# Schematics.net
KiCad netlist of a schematic drawn in EasyEDA
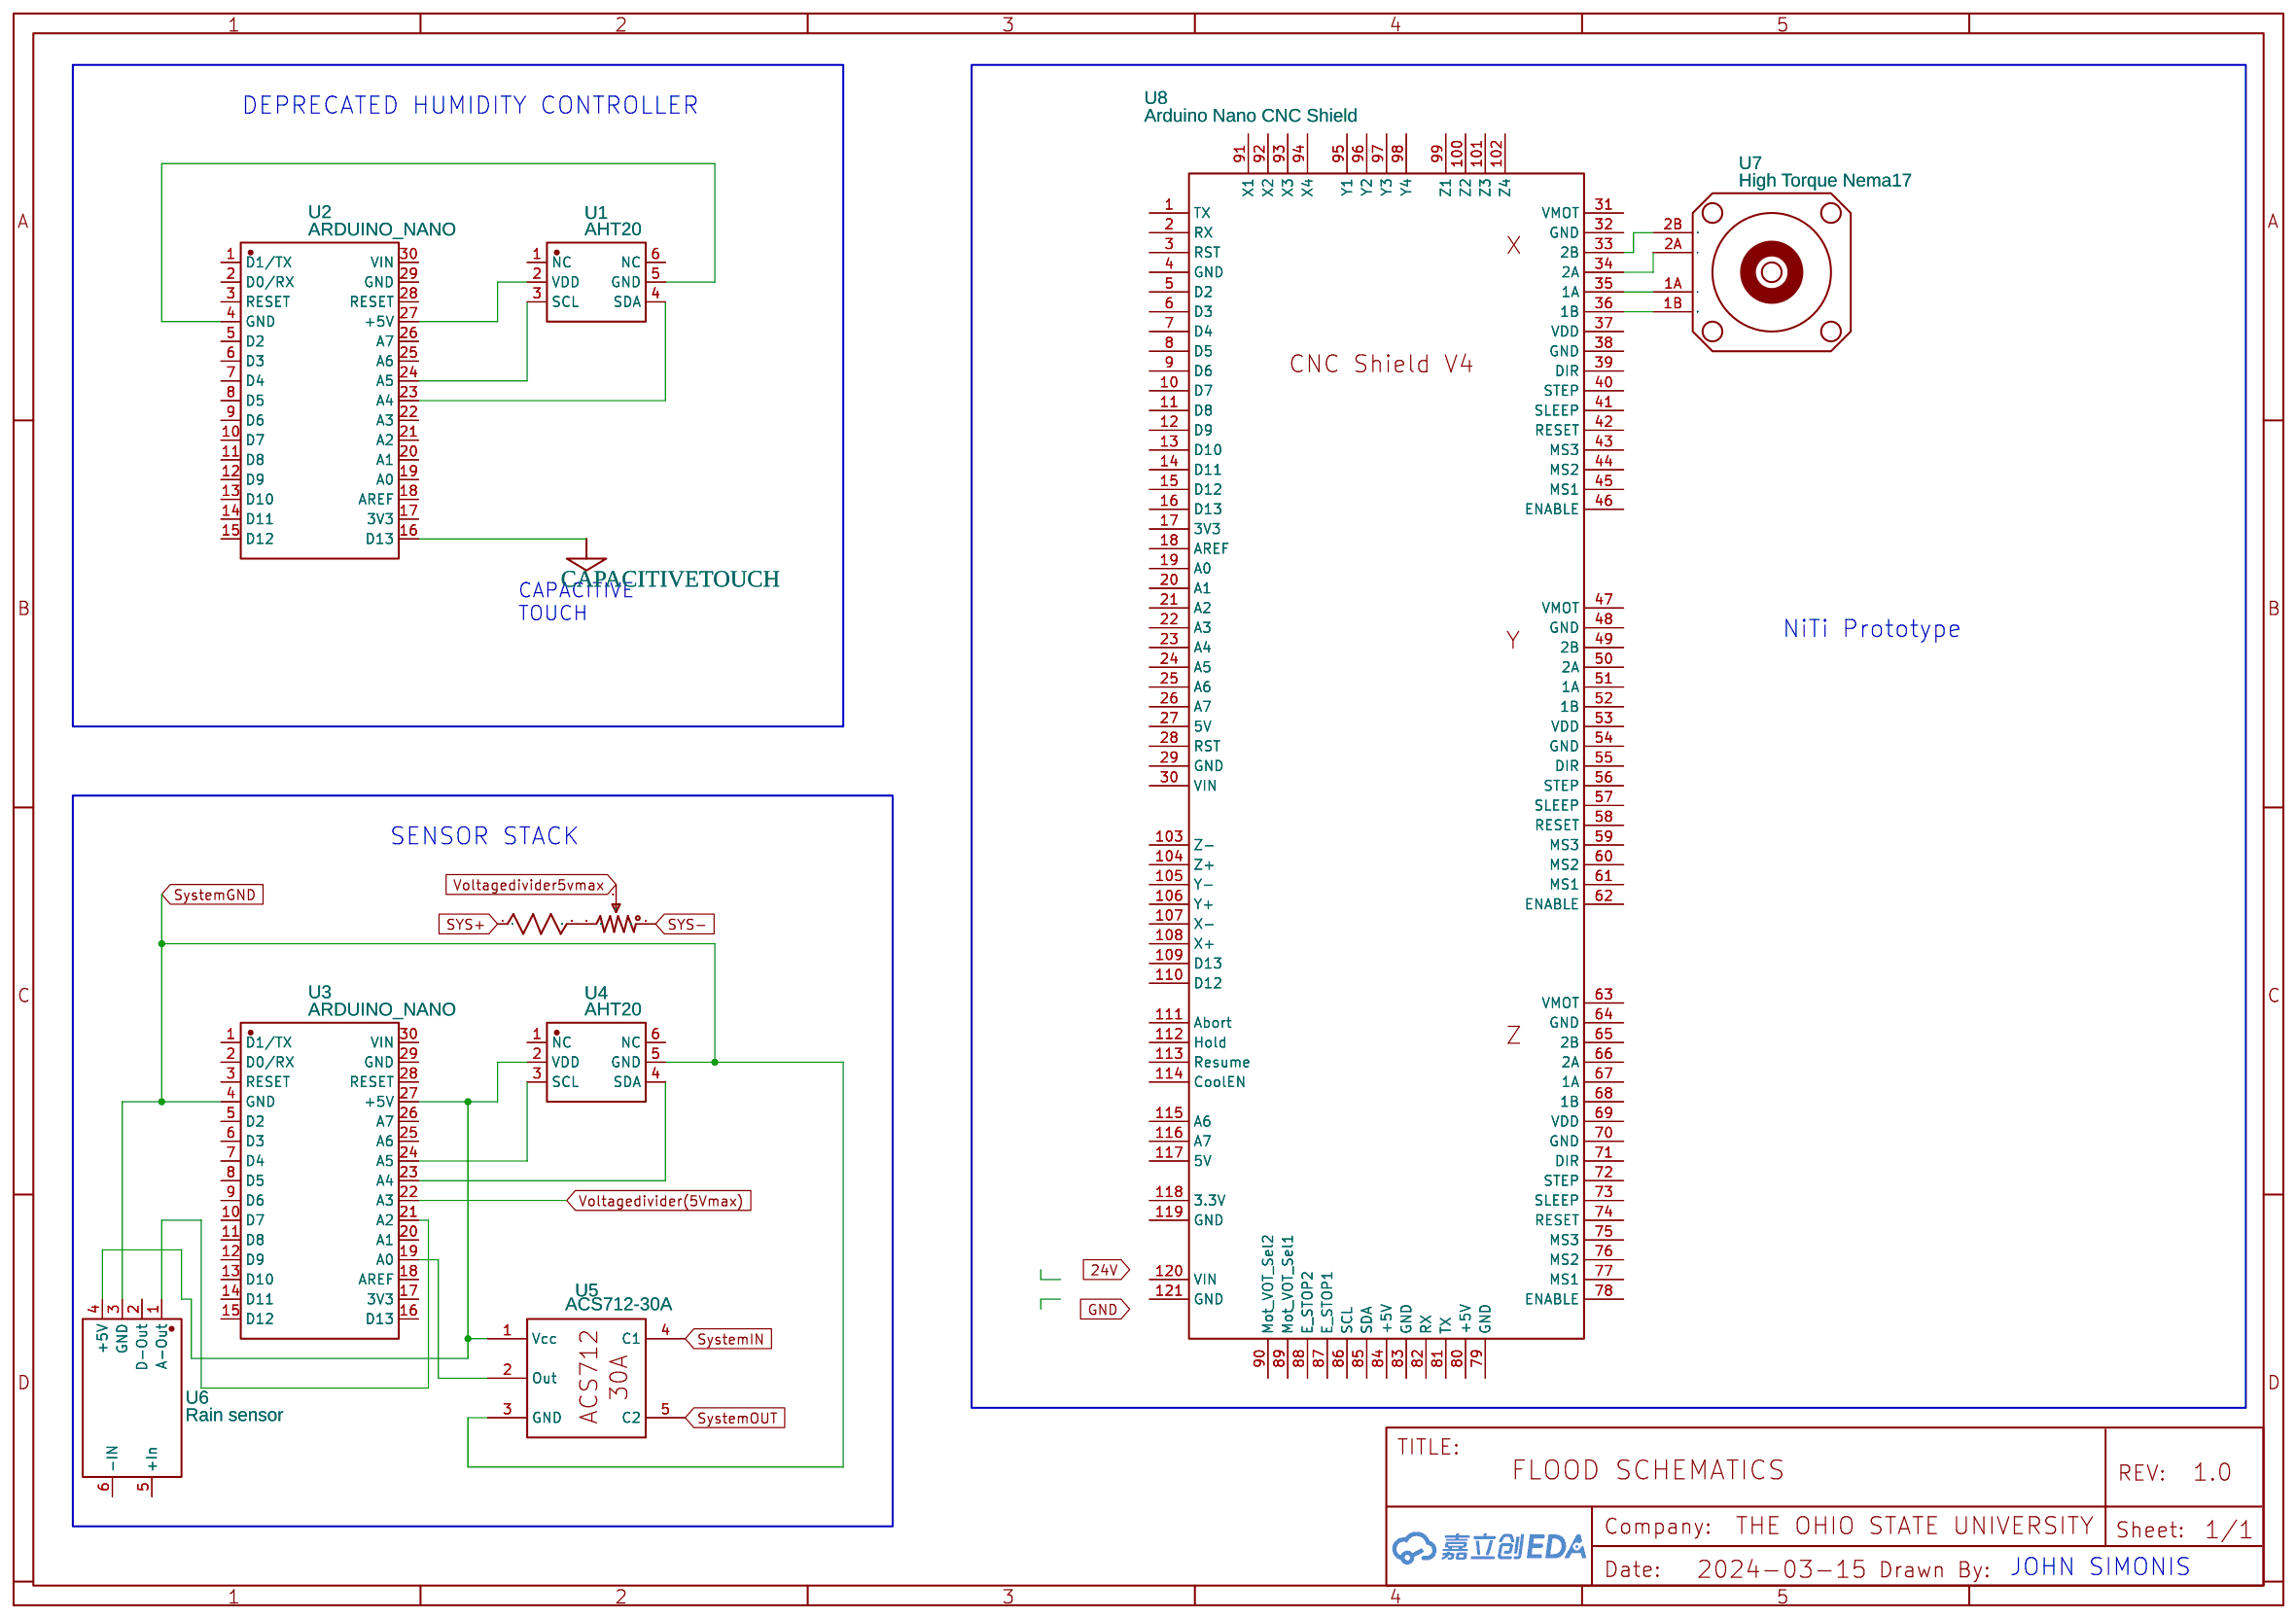
[diagram p0: schematic sheet]

(export (version "E")
  (design (tool "Eeschema 10.0.6"))
  (components
    (comp (ref "R1") (value "1k") (libsource (lib "") (part "R_0603_US")))
    (comp (ref "RP1") (value "R_3386P_US") (libsource (lib "") (part "R_3386P_US")))
    (comp (ref "U1")
      (value "AHT20")
      (fields (field (name "Manufacturer") "广州奥松"))
      (libsource (lib "") (part "AHT20"))
    )
    (comp (ref "U2") (value "ARDUINO_NANO") (libsource (lib "") (part "ARDUINO_NANO")))
    (comp (ref "U3") (value "ARDUINO_NANO") (libsource (lib "") (part "ARDUINO_NANO")))
    (comp (ref "U4")
      (value "AHT20")
      (fields (field (name "Manufacturer") "广州奥松"))
      (libsource (lib "") (part "AHT20"))
    )
    (comp (ref "U5") (value "ACS712-30A") (libsource (lib "") (part "ACS712-30A")))
    (comp (ref "U6") (value "Rain sensor") (libsource (lib "") (part "Rain sensor")))
    (comp (ref "U7") (value "High Torque Nema17") (libsource (lib "") (part "Nema17")))
    (comp (ref "U8") (value "Arduino Nano CNC Shield") (libsource (lib "") (part "Arduino Nano CNC Shield")))
  )
  (nets
    (net (code "2") (name "CAPACITIVETOUCH") (class "Default")
      (node (ref "U2") (pin "16") (pinfunction "D13_16") (pintype "unspecified"))
    )
    (net (code "4") (name "Net-(R1-Pad2)") (class "Default")
      (node (ref "R1") (pin "2") (pinfunction "2_2") (pintype "unspecified"))
      (node (ref "RP1") (pin "3") (pinfunction "3_3") (pintype "unspecified"))
    )
    (net (code "5") (name "Net-(U1-GND)") (class "Default")
      (node (ref "U1") (pin "5") (pinfunction "GND_5") (pintype "unspecified"))
      (node (ref "U2") (pin "4") (pinfunction "GND_4") (pintype "unspecified"))
    )
    (net (code "6") (name "Net-(U1-SCL)") (class "Default")
      (node (ref "U1") (pin "3") (pinfunction "SCL_3") (pintype "unspecified"))
      (node (ref "U2") (pin "24") (pinfunction "A5_24") (pintype "unspecified"))
    )
    (net (code "7") (name "Net-(U1-SDA)") (class "Default")
      (node (ref "U1") (pin "4") (pinfunction "SDA_4") (pintype "unspecified"))
      (node (ref "U2") (pin "23") (pinfunction "A4_23") (pintype "unspecified"))
    )
    (net (code "8") (name "Net-(U1-VDD)") (class "Default")
      (node (ref "U1") (pin "2") (pinfunction "VDD_2") (pintype "unspecified"))
      (node (ref "U2") (pin "27") (pinfunction "+5V_27") (pintype "unspecified"))
    )
    (net (code "9") (name "Net-(U3-+5V)") (class "Default")
      (node (ref "U3") (pin "27") (pinfunction "+5V_27") (pintype "unspecified"))
      (node (ref "U4") (pin "2") (pinfunction "VDD_2") (pintype "unspecified"))
      (node (ref "U5") (pin "1") (pinfunction "Vcc_1") (pintype "unspecified"))
      (node (ref "U6") (pin "4") (pinfunction "+5V_4") (pintype "unspecified"))
    )
    (net (code "10") (name "Net-(U3-A0)") (class "Default")
      (node (ref "U3") (pin "19") (pinfunction "A0_19") (pintype "unspecified"))
      (node (ref "U5") (pin "2") (pinfunction "Out_2") (pintype "unspecified"))
    )
    (net (code "11") (name "Net-(U3-A2)") (class "Default")
      (node (ref "U3") (pin "21") (pinfunction "A2_21") (pintype "unspecified"))
      (node (ref "U6") (pin "1") (pinfunction "A-Out_1") (pintype "unspecified"))
    )
    (net (code "12") (name "Net-(U3-A4)") (class "Default")
      (node (ref "U3") (pin "23") (pinfunction "A4_23") (pintype "unspecified"))
      (node (ref "U4") (pin "4") (pinfunction "SDA_4") (pintype "unspecified"))
    )
    (net (code "13") (name "Net-(U3-A5)") (class "Default")
      (node (ref "U3") (pin "24") (pinfunction "A5_24") (pintype "unspecified"))
      (node (ref "U4") (pin "3") (pinfunction "SCL_3") (pintype "unspecified"))
    )
    (net (code "14") (name "Net-(U7-A-Pad1A)") (class "Default")
      (node (ref "U7") (pin "1A") (pinfunction "A_1A") (pintype "unspecified"))
      (node (ref "U8") (pin "35") (pinfunction "1A_35") (pintype "unspecified"))
    )
    (net (code "15") (name "Net-(U7-A-Pad2A)") (class "Default")
      (node (ref "U7") (pin "2A") (pinfunction "A_2A") (pintype "unspecified"))
      (node (ref "U8") (pin "34") (pinfunction "2A_34") (pintype "unspecified"))
    )
    (net (code "16") (name "Net-(U7-B-Pad1B)") (class "Default")
      (node (ref "U7") (pin "1B") (pinfunction "B_1B") (pintype "unspecified"))
      (node (ref "U8") (pin "36") (pinfunction "1B_36") (pintype "unspecified"))
    )
    (net (code "17") (name "Net-(U7-B-Pad2B)") (class "Default")
      (node (ref "U7") (pin "2B") (pinfunction "B_2B") (pintype "unspecified"))
      (node (ref "U8") (pin "33") (pinfunction "2B_33") (pintype "unspecified"))
    )
    (net (code "18") (name "SYS+") (class "Default")
      (node (ref "R1") (pin "1") (pinfunction "1_1") (pintype "unspecified"))
    )
    (net (code "19") (name "SYS-") (class "Default")
      (node (ref "RP1") (pin "1") (pinfunction "1_1") (pintype "unspecified"))
    )
    (net (code "20") (name "SystemGND") (class "Default")
      (node (ref "U3") (pin "4") (pinfunction "GND_4") (pintype "unspecified"))
      (node (ref "U4") (pin "5") (pinfunction "GND_5") (pintype "unspecified"))
      (node (ref "U5") (pin "3") (pinfunction "GND_3") (pintype "unspecified"))
      (node (ref "U6") (pin "3") (pinfunction "GND_3") (pintype "unspecified"))
    )
    (net (code "21") (name "SystemIN") (class "Default")
      (node (ref "U5") (pin "4") (pinfunction "C1_4") (pintype "unspecified"))
    )
    (net (code "22") (name "SystemOUT") (class "Default")
      (node (ref "U5") (pin "5") (pinfunction "C2_5") (pintype "unspecified"))
    )
    (net (code "23") (name "Voltagedivider(5Vmax)") (class "Default")
      (node (ref "U3") (pin "22") (pinfunction "A3_22") (pintype "unspecified"))
    )
    (net (code "24") (name "Voltagedivider5vmax") (class "Default")
      (node (ref "RP1") (pin "2") (pinfunction "2_2") (pintype "unspecified"))
    )
    (net (code "25") (name "unconnected-(U1-NC-Pad1)") (class "Default")
      (node (ref "U1") (pin "1") (pinfunction "NC_1") (pintype "unspecified"))
    )
    (net (code "26") (name "unconnected-(U1-NC-Pad6)") (class "Default")
      (node (ref "U1") (pin "6") (pinfunction "NC_6") (pintype "unspecified"))
    )
    (net (code "27") (name "unconnected-(U2-3V3-Pad17)") (class "Default")
      (node (ref "U2") (pin "17") (pinfunction "3V3_17") (pintype "unspecified"))
    )
    (net (code "28") (name "unconnected-(U2-A0-Pad19)") (class "Default")
      (node (ref "U2") (pin "19") (pinfunction "A0_19") (pintype "unspecified"))
    )
    (net (code "29") (name "unconnected-(U2-A1-Pad20)") (class "Default")
      (node (ref "U2") (pin "20") (pinfunction "A1_20") (pintype "unspecified"))
    )
    (net (code "30") (name "unconnected-(U2-A2-Pad21)") (class "Default")
      (node (ref "U2") (pin "21") (pinfunction "A2_21") (pintype "unspecified"))
    )
    (net (code "31") (name "unconnected-(U2-A3-Pad22)") (class "Default")
      (node (ref "U2") (pin "22") (pinfunction "A3_22") (pintype "unspecified"))
    )
    (net (code "32") (name "unconnected-(U2-A6-Pad25)") (class "Default")
      (node (ref "U2") (pin "25") (pinfunction "A6_25") (pintype "unspecified"))
    )
    (net (code "33") (name "unconnected-(U2-A7-Pad26)") (class "Default")
      (node (ref "U2") (pin "26") (pinfunction "A7_26") (pintype "unspecified"))
    )
    (net (code "34") (name "unconnected-(U2-AREF-Pad18)") (class "Default")
      (node (ref "U2") (pin "18") (pinfunction "AREF_18") (pintype "unspecified"))
    )
    (net (code "35") (name "unconnected-(U2-D0{slash}RX-Pad2)") (class "Default")
      (node (ref "U2") (pin "2") (pinfunction "D0/RX_2") (pintype "unspecified"))
    )
    (net (code "36") (name "unconnected-(U2-D1{slash}TX-Pad1)") (class "Default")
      (node (ref "U2") (pin "1") (pinfunction "D1/TX_1") (pintype "unspecified"))
    )
    (net (code "37") (name "unconnected-(U2-D2-Pad5)") (class "Default")
      (node (ref "U2") (pin "5") (pinfunction "D2_5") (pintype "unspecified"))
    )
    (net (code "38") (name "unconnected-(U2-D3-Pad6)") (class "Default")
      (node (ref "U2") (pin "6") (pinfunction "D3_6") (pintype "unspecified"))
    )
    (net (code "39") (name "unconnected-(U2-D4-Pad7)") (class "Default")
      (node (ref "U2") (pin "7") (pinfunction "D4_7") (pintype "unspecified"))
    )
    (net (code "40") (name "unconnected-(U2-D5-Pad8)") (class "Default")
      (node (ref "U2") (pin "8") (pinfunction "D5_8") (pintype "unspecified"))
    )
    (net (code "41") (name "unconnected-(U2-D6-Pad9)") (class "Default")
      (node (ref "U2") (pin "9") (pinfunction "D6_9") (pintype "unspecified"))
    )
    (net (code "42") (name "unconnected-(U2-D7-Pad10)") (class "Default")
      (node (ref "U2") (pin "10") (pinfunction "D7_10") (pintype "unspecified"))
    )
    (net (code "43") (name "unconnected-(U2-D8-Pad11)") (class "Default")
      (node (ref "U2") (pin "11") (pinfunction "D8_11") (pintype "unspecified"))
    )
    (net (code "44") (name "unconnected-(U2-D9-Pad12)") (class "Default")
      (node (ref "U2") (pin "12") (pinfunction "D9_12") (pintype "unspecified"))
    )
    (net (code "45") (name "unconnected-(U2-D10-Pad13)") (class "Default")
      (node (ref "U2") (pin "13") (pinfunction "D10_13") (pintype "unspecified"))
    )
    (net (code "46") (name "unconnected-(U2-D11-Pad14)") (class "Default")
      (node (ref "U2") (pin "14") (pinfunction "D11_14") (pintype "unspecified"))
    )
    (net (code "47") (name "unconnected-(U2-D12-Pad15)") (class "Default")
      (node (ref "U2") (pin "15") (pinfunction "D12_15") (pintype "unspecified"))
    )
    (net (code "48") (name "unconnected-(U2-GND-Pad29)") (class "Default")
      (node (ref "U2") (pin "29") (pinfunction "GND_29") (pintype "unspecified"))
    )
    (net (code "49") (name "unconnected-(U2-RESET-Pad3)") (class "Default")
      (node (ref "U2") (pin "3") (pinfunction "RESET_3") (pintype "unspecified"))
    )
    (net (code "50") (name "unconnected-(U2-RESET-Pad28)") (class "Default")
      (node (ref "U2") (pin "28") (pinfunction "RESET_28") (pintype "unspecified"))
    )
    (net (code "51") (name "unconnected-(U2-VIN-Pad30)") (class "Default")
      (node (ref "U2") (pin "30") (pinfunction "VIN_30") (pintype "unspecified"))
    )
    (net (code "52") (name "unconnected-(U3-3V3-Pad17)") (class "Default")
      (node (ref "U3") (pin "17") (pinfunction "3V3_17") (pintype "unspecified"))
    )
    (net (code "53") (name "unconnected-(U3-A1-Pad20)") (class "Default")
      (node (ref "U3") (pin "20") (pinfunction "A1_20") (pintype "unspecified"))
    )
    (net (code "54") (name "unconnected-(U3-A6-Pad25)") (class "Default")
      (node (ref "U3") (pin "25") (pinfunction "A6_25") (pintype "unspecified"))
    )
    (net (code "55") (name "unconnected-(U3-A7-Pad26)") (class "Default")
      (node (ref "U3") (pin "26") (pinfunction "A7_26") (pintype "unspecified"))
    )
    (net (code "56") (name "unconnected-(U3-AREF-Pad18)") (class "Default")
      (node (ref "U3") (pin "18") (pinfunction "AREF_18") (pintype "unspecified"))
    )
    (net (code "57") (name "unconnected-(U3-D0{slash}RX-Pad2)") (class "Default")
      (node (ref "U3") (pin "2") (pinfunction "D0/RX_2") (pintype "unspecified"))
    )
    (net (code "58") (name "unconnected-(U3-D1{slash}TX-Pad1)") (class "Default")
      (node (ref "U3") (pin "1") (pinfunction "D1/TX_1") (pintype "unspecified"))
    )
    (net (code "59") (name "unconnected-(U3-D2-Pad5)") (class "Default")
      (node (ref "U3") (pin "5") (pinfunction "D2_5") (pintype "unspecified"))
    )
    (net (code "60") (name "unconnected-(U3-D3-Pad6)") (class "Default")
      (node (ref "U3") (pin "6") (pinfunction "D3_6") (pintype "unspecified"))
    )
    (net (code "61") (name "unconnected-(U3-D4-Pad7)") (class "Default")
      (node (ref "U3") (pin "7") (pinfunction "D4_7") (pintype "unspecified"))
    )
    (net (code "62") (name "unconnected-(U3-D5-Pad8)") (class "Default")
      (node (ref "U3") (pin "8") (pinfunction "D5_8") (pintype "unspecified"))
    )
    (net (code "63") (name "unconnected-(U3-D6-Pad9)") (class "Default")
      (node (ref "U3") (pin "9") (pinfunction "D6_9") (pintype "unspecified"))
    )
    (net (code "64") (name "unconnected-(U3-D7-Pad10)") (class "Default")
      (node (ref "U3") (pin "10") (pinfunction "D7_10") (pintype "unspecified"))
    )
    (net (code "65") (name "unconnected-(U3-D8-Pad11)") (class "Default")
      (node (ref "U3") (pin "11") (pinfunction "D8_11") (pintype "unspecified"))
    )
    (net (code "66") (name "unconnected-(U3-D9-Pad12)") (class "Default")
      (node (ref "U3") (pin "12") (pinfunction "D9_12") (pintype "unspecified"))
    )
    (net (code "67") (name "unconnected-(U3-D10-Pad13)") (class "Default")
      (node (ref "U3") (pin "13") (pinfunction "D10_13") (pintype "unspecified"))
    )
    (net (code "68") (name "unconnected-(U3-D11-Pad14)") (class "Default")
      (node (ref "U3") (pin "14") (pinfunction "D11_14") (pintype "unspecified"))
    )
    (net (code "69") (name "unconnected-(U3-D12-Pad15)") (class "Default")
      (node (ref "U3") (pin "15") (pinfunction "D12_15") (pintype "unspecified"))
    )
    (net (code "70") (name "unconnected-(U3-D13-Pad16)") (class "Default")
      (node (ref "U3") (pin "16") (pinfunction "D13_16") (pintype "unspecified"))
    )
    (net (code "71") (name "unconnected-(U3-GND-Pad29)") (class "Default")
      (node (ref "U3") (pin "29") (pinfunction "GND_29") (pintype "unspecified"))
    )
    (net (code "72") (name "unconnected-(U3-RESET-Pad3)") (class "Default")
      (node (ref "U3") (pin "3") (pinfunction "RESET_3") (pintype "unspecified"))
    )
    (net (code "73") (name "unconnected-(U3-RESET-Pad28)") (class "Default")
      (node (ref "U3") (pin "28") (pinfunction "RESET_28") (pintype "unspecified"))
    )
    (net (code "74") (name "unconnected-(U3-VIN-Pad30)") (class "Default")
      (node (ref "U3") (pin "30") (pinfunction "VIN_30") (pintype "unspecified"))
    )
    (net (code "75") (name "unconnected-(U4-NC-Pad1)") (class "Default")
      (node (ref "U4") (pin "1") (pinfunction "NC_1") (pintype "unspecified"))
    )
    (net (code "76") (name "unconnected-(U4-NC-Pad6)") (class "Default")
      (node (ref "U4") (pin "6") (pinfunction "NC_6") (pintype "unspecified"))
    )
    (net (code "77") (name "unconnected-(U6-+In-Pad5)") (class "Default")
      (node (ref "U6") (pin "5") (pinfunction "+In_5") (pintype "unspecified"))
    )
    (net (code "78") (name "unconnected-(U6--IN-Pad6)") (class "Default")
      (node (ref "U6") (pin "6") (pinfunction "-IN_6") (pintype "unspecified"))
    )
    (net (code "79") (name "unconnected-(U6-D-Out-Pad2)") (class "Default")
      (node (ref "U6") (pin "2") (pinfunction "D-Out_2") (pintype "unspecified"))
    )
    (net (code "80") (name "unconnected-(U8-+5V-Pad80)") (class "Default")
      (node (ref "U8") (pin "80") (pinfunction "+5V_80") (pintype "unspecified"))
    )
    (net (code "81") (name "unconnected-(U8-+5V-Pad84)") (class "Default")
      (node (ref "U8") (pin "84") (pinfunction "+5V_84") (pintype "unspecified"))
    )
    (net (code "82") (name "unconnected-(U8-1A-Pad51)") (class "Default")
      (node (ref "U8") (pin "51") (pinfunction "1A_51") (pintype "unspecified"))
    )
    (net (code "83") (name "unconnected-(U8-1A-Pad67)") (class "Default")
      (node (ref "U8") (pin "67") (pinfunction "1A_67") (pintype "unspecified"))
    )
    (net (code "84") (name "unconnected-(U8-1B-Pad52)") (class "Default")
      (node (ref "U8") (pin "52") (pinfunction "1B_52") (pintype "unspecified"))
    )
    (net (code "85") (name "unconnected-(U8-1B-Pad68)") (class "Default")
      (node (ref "U8") (pin "68") (pinfunction "1B_68") (pintype "unspecified"))
    )
    (net (code "86") (name "unconnected-(U8-2A-Pad50)") (class "Default")
      (node (ref "U8") (pin "50") (pinfunction "2A_50") (pintype "unspecified"))
    )
    (net (code "87") (name "unconnected-(U8-2A-Pad66)") (class "Default")
      (node (ref "U8") (pin "66") (pinfunction "2A_66") (pintype "unspecified"))
    )
    (net (code "88") (name "unconnected-(U8-2B-Pad49)") (class "Default")
      (node (ref "U8") (pin "49") (pinfunction "2B_49") (pintype "unspecified"))
    )
    (net (code "89") (name "unconnected-(U8-2B-Pad65)") (class "Default")
      (node (ref "U8") (pin "65") (pinfunction "2B_65") (pintype "unspecified"))
    )
    (net (code "90") (name "unconnected-(U8-3.3V-Pad118)") (class "Default")
      (node (ref "U8") (pin "118") (pinfunction "3.3V_118") (pintype "unspecified"))
    )
    (net (code "91") (name "unconnected-(U8-3V3-Pad17)") (class "Default")
      (node (ref "U8") (pin "17") (pinfunction "3V3_17") (pintype "unspecified"))
    )
    (net (code "92") (name "unconnected-(U8-5V-Pad27)") (class "Default")
      (node (ref "U8") (pin "27") (pinfunction "5V_27") (pintype "unspecified"))
    )
    (net (code "93") (name "unconnected-(U8-5V-Pad117)") (class "Default")
      (node (ref "U8") (pin "117") (pinfunction "5V_117") (pintype "unspecified"))
    )
    (net (code "94") (name "unconnected-(U8-A0-Pad19)") (class "Default")
      (node (ref "U8") (pin "19") (pinfunction "A0_19") (pintype "unspecified"))
    )
    (net (code "95") (name "unconnected-(U8-A1-Pad20)") (class "Default")
      (node (ref "U8") (pin "20") (pinfunction "A1_20") (pintype "unspecified"))
    )
    (net (code "96") (name "unconnected-(U8-A2-Pad21)") (class "Default")
      (node (ref "U8") (pin "21") (pinfunction "A2_21") (pintype "unspecified"))
    )
    (net (code "97") (name "unconnected-(U8-A3-Pad22)") (class "Default")
      (node (ref "U8") (pin "22") (pinfunction "A3_22") (pintype "unspecified"))
    )
    (net (code "98") (name "unconnected-(U8-A4-Pad23)") (class "Default")
      (node (ref "U8") (pin "23") (pinfunction "A4_23") (pintype "unspecified"))
    )
    (net (code "99") (name "unconnected-(U8-A5-Pad24)") (class "Default")
      (node (ref "U8") (pin "24") (pinfunction "A5_24") (pintype "unspecified"))
    )
    (net (code "100") (name "unconnected-(U8-A6-Pad25)") (class "Default")
      (node (ref "U8") (pin "25") (pinfunction "A6_25") (pintype "unspecified"))
    )
    (net (code "101") (name "unconnected-(U8-A6-Pad115)") (class "Default")
      (node (ref "U8") (pin "115") (pinfunction "A6_115") (pintype "unspecified"))
    )
    (net (code "102") (name "unconnected-(U8-A7-Pad26)") (class "Default")
      (node (ref "U8") (pin "26") (pinfunction "A7_26") (pintype "unspecified"))
    )
    (net (code "103") (name "unconnected-(U8-A7-Pad116)") (class "Default")
      (node (ref "U8") (pin "116") (pinfunction "A7_116") (pintype "unspecified"))
    )
    (net (code "104") (name "unconnected-(U8-AREF-Pad18)") (class "Default")
      (node (ref "U8") (pin "18") (pinfunction "AREF_18") (pintype "unspecified"))
    )
    (net (code "105") (name "unconnected-(U8-Abort-Pad111)") (class "Default")
      (node (ref "U8") (pin "111") (pinfunction "Abort_111") (pintype "unspecified"))
    )
    (net (code "106") (name "unconnected-(U8-CoolEN-Pad114)") (class "Default")
      (node (ref "U8") (pin "114") (pinfunction "CoolEN_114") (pintype "unspecified"))
    )
    (net (code "107") (name "unconnected-(U8-D2-Pad5)") (class "Default")
      (node (ref "U8") (pin "5") (pinfunction "D2_5") (pintype "unspecified"))
    )
    (net (code "108") (name "unconnected-(U8-D3-Pad6)") (class "Default")
      (node (ref "U8") (pin "6") (pinfunction "D3_6") (pintype "unspecified"))
    )
    (net (code "109") (name "unconnected-(U8-D4-Pad7)") (class "Default")
      (node (ref "U8") (pin "7") (pinfunction "D4_7") (pintype "unspecified"))
    )
    (net (code "110") (name "unconnected-(U8-D5-Pad8)") (class "Default")
      (node (ref "U8") (pin "8") (pinfunction "D5_8") (pintype "unspecified"))
    )
    (net (code "111") (name "unconnected-(U8-D6-Pad9)") (class "Default")
      (node (ref "U8") (pin "9") (pinfunction "D6_9") (pintype "unspecified"))
    )
    (net (code "112") (name "unconnected-(U8-D7-Pad10)") (class "Default")
      (node (ref "U8") (pin "10") (pinfunction "D7_10") (pintype "unspecified"))
    )
    (net (code "113") (name "unconnected-(U8-D8-Pad11)") (class "Default")
      (node (ref "U8") (pin "11") (pinfunction "D8_11") (pintype "unspecified"))
    )
    (net (code "114") (name "unconnected-(U8-D9-Pad12)") (class "Default")
      (node (ref "U8") (pin "12") (pinfunction "D9_12") (pintype "unspecified"))
    )
    (net (code "115") (name "unconnected-(U8-D10-Pad13)") (class "Default")
      (node (ref "U8") (pin "13") (pinfunction "D10_13") (pintype "unspecified"))
    )
    (net (code "116") (name "unconnected-(U8-D11-Pad14)") (class "Default")
      (node (ref "U8") (pin "14") (pinfunction "D11_14") (pintype "unspecified"))
    )
    (net (code "117") (name "unconnected-(U8-D12-Pad15)") (class "Default")
      (node (ref "U8") (pin "15") (pinfunction "D12_15") (pintype "unspecified"))
    )
    (net (code "118") (name "unconnected-(U8-D12-Pad110)") (class "Default")
      (node (ref "U8") (pin "110") (pinfunction "D12_110") (pintype "unspecified"))
    )
    (net (code "119") (name "unconnected-(U8-D13-Pad16)") (class "Default")
      (node (ref "U8") (pin "16") (pinfunction "D13_16") (pintype "unspecified"))
    )
    (net (code "120") (name "unconnected-(U8-D13-Pad109)") (class "Default")
      (node (ref "U8") (pin "109") (pinfunction "D13_109") (pintype "unspecified"))
    )
    (net (code "121") (name "unconnected-(U8-DIR-Pad39)") (class "Default")
      (node (ref "U8") (pin "39") (pinfunction "DIR_39") (pintype "unspecified"))
    )
    (net (code "122") (name "unconnected-(U8-DIR-Pad55)") (class "Default")
      (node (ref "U8") (pin "55") (pinfunction "DIR_55") (pintype "unspecified"))
    )
    (net (code "123") (name "unconnected-(U8-DIR-Pad71)") (class "Default")
      (node (ref "U8") (pin "71") (pinfunction "DIR_71") (pintype "unspecified"))
    )
    (net (code "124") (name "unconnected-(U8-ENABLE-Pad46)") (class "Default")
      (node (ref "U8") (pin "46") (pinfunction "ENABLE_46") (pintype "unspecified"))
    )
    (net (code "125") (name "unconnected-(U8-ENABLE-Pad62)") (class "Default")
      (node (ref "U8") (pin "62") (pinfunction "ENABLE_62") (pintype "unspecified"))
    )
    (net (code "126") (name "unconnected-(U8-ENABLE-Pad78)") (class "Default")
      (node (ref "U8") (pin "78") (pinfunction "ENABLE_78") (pintype "unspecified"))
    )
    (net (code "127") (name "unconnected-(U8-E_STOP1-Pad87)") (class "Default")
      (node (ref "U8") (pin "87") (pinfunction "E_STOP1_87") (pintype "unspecified"))
    )
    (net (code "128") (name "unconnected-(U8-E_STOP2-Pad88)") (class "Default")
      (node (ref "U8") (pin "88") (pinfunction "E_STOP2_88") (pintype "unspecified"))
    )
    (net (code "129") (name "unconnected-(U8-GND-Pad4)") (class "Default")
      (node (ref "U8") (pin "4") (pinfunction "GND_4") (pintype "unspecified"))
    )
    (net (code "130") (name "unconnected-(U8-GND-Pad29)") (class "Default")
      (node (ref "U8") (pin "29") (pinfunction "GND_29") (pintype "unspecified"))
    )
    (net (code "131") (name "unconnected-(U8-GND-Pad32)") (class "Default")
      (node (ref "U8") (pin "32") (pinfunction "GND_32") (pintype "unspecified"))
    )
    (net (code "132") (name "unconnected-(U8-GND-Pad38)") (class "Default")
      (node (ref "U8") (pin "38") (pinfunction "GND_38") (pintype "unspecified"))
    )
    (net (code "133") (name "unconnected-(U8-GND-Pad48)") (class "Default")
      (node (ref "U8") (pin "48") (pinfunction "GND_48") (pintype "unspecified"))
    )
    (net (code "134") (name "unconnected-(U8-GND-Pad54)") (class "Default")
      (node (ref "U8") (pin "54") (pinfunction "GND_54") (pintype "unspecified"))
    )
    (net (code "135") (name "unconnected-(U8-GND-Pad64)") (class "Default")
      (node (ref "U8") (pin "64") (pinfunction "GND_64") (pintype "unspecified"))
    )
    (net (code "136") (name "unconnected-(U8-GND-Pad70)") (class "Default")
      (node (ref "U8") (pin "70") (pinfunction "GND_70") (pintype "unspecified"))
    )
    (net (code "137") (name "unconnected-(U8-GND-Pad79)") (class "Default")
      (node (ref "U8") (pin "79") (pinfunction "GND_79") (pintype "unspecified"))
    )
    (net (code "138") (name "unconnected-(U8-GND-Pad83)") (class "Default")
      (node (ref "U8") (pin "83") (pinfunction "GND_83") (pintype "unspecified"))
    )
    (net (code "139") (name "unconnected-(U8-GND-Pad119)") (class "Default")
      (node (ref "U8") (pin "119") (pinfunction "GND_119") (pintype "unspecified"))
    )
    (net (code "140") (name "unconnected-(U8-GND-Pad121)") (class "Default")
      (node (ref "U8") (pin "121") (pinfunction "GND_121") (pintype "unspecified"))
    )
    (net (code "141") (name "unconnected-(U8-Hold-Pad112)") (class "Default")
      (node (ref "U8") (pin "112") (pinfunction "Hold_112") (pintype "unspecified"))
    )
    (net (code "142") (name "unconnected-(U8-MS1-Pad45)") (class "Default")
      (node (ref "U8") (pin "45") (pinfunction "MS1_45") (pintype "unspecified"))
    )
    (net (code "143") (name "unconnected-(U8-MS1-Pad61)") (class "Default")
      (node (ref "U8") (pin "61") (pinfunction "MS1_61") (pintype "unspecified"))
    )
    (net (code "144") (name "unconnected-(U8-MS1-Pad77)") (class "Default")
      (node (ref "U8") (pin "77") (pinfunction "MS1_77") (pintype "unspecified"))
    )
    (net (code "145") (name "unconnected-(U8-MS2-Pad44)") (class "Default")
      (node (ref "U8") (pin "44") (pinfunction "MS2_44") (pintype "unspecified"))
    )
    (net (code "146") (name "unconnected-(U8-MS2-Pad60)") (class "Default")
      (node (ref "U8") (pin "60") (pinfunction "MS2_60") (pintype "unspecified"))
    )
    (net (code "147") (name "unconnected-(U8-MS2-Pad76)") (class "Default")
      (node (ref "U8") (pin "76") (pinfunction "MS2_76") (pintype "unspecified"))
    )
    (net (code "148") (name "unconnected-(U8-MS3-Pad43)") (class "Default")
      (node (ref "U8") (pin "43") (pinfunction "MS3_43") (pintype "unspecified"))
    )
    (net (code "149") (name "unconnected-(U8-MS3-Pad59)") (class "Default")
      (node (ref "U8") (pin "59") (pinfunction "MS3_59") (pintype "unspecified"))
    )
    (net (code "150") (name "unconnected-(U8-MS3-Pad75)") (class "Default")
      (node (ref "U8") (pin "75") (pinfunction "MS3_75") (pintype "unspecified"))
    )
    (net (code "151") (name "unconnected-(U8-Mot_VOT_Sel1-Pad89)") (class "Default")
      (node (ref "U8") (pin "89") (pinfunction "Mot_VOT_Sel1_89") (pintype "unspecified"))
    )
    (net (code "152") (name "unconnected-(U8-Mot_VOT_Sel2-Pad90)") (class "Default")
      (node (ref "U8") (pin "90") (pinfunction "Mot_VOT_Sel2_90") (pintype "unspecified"))
    )
    (net (code "153") (name "unconnected-(U8-RESET-Pad42)") (class "Default")
      (node (ref "U8") (pin "42") (pinfunction "RESET_42") (pintype "unspecified"))
    )
    (net (code "154") (name "unconnected-(U8-RESET-Pad58)") (class "Default")
      (node (ref "U8") (pin "58") (pinfunction "RESET_58") (pintype "unspecified"))
    )
    (net (code "155") (name "unconnected-(U8-RESET-Pad74)") (class "Default")
      (node (ref "U8") (pin "74") (pinfunction "RESET_74") (pintype "unspecified"))
    )
    (net (code "156") (name "unconnected-(U8-RST-Pad3)") (class "Default")
      (node (ref "U8") (pin "3") (pinfunction "RST_3") (pintype "unspecified"))
    )
    (net (code "157") (name "unconnected-(U8-RST-Pad28)") (class "Default")
      (node (ref "U8") (pin "28") (pinfunction "RST_28") (pintype "unspecified"))
    )
    (net (code "158") (name "unconnected-(U8-RX-Pad2)") (class "Default")
      (node (ref "U8") (pin "2") (pinfunction "RX_2") (pintype "unspecified"))
    )
    (net (code "159") (name "unconnected-(U8-RX-Pad82)") (class "Default")
      (node (ref "U8") (pin "82") (pinfunction "RX_82") (pintype "unspecified"))
    )
    (net (code "160") (name "unconnected-(U8-Resume-Pad113)") (class "Default")
      (node (ref "U8") (pin "113") (pinfunction "Resume_113") (pintype "unspecified"))
    )
    (net (code "161") (name "unconnected-(U8-SCL-Pad86)") (class "Default")
      (node (ref "U8") (pin "86") (pinfunction "SCL_86") (pintype "unspecified"))
    )
    (net (code "162") (name "unconnected-(U8-SDA-Pad85)") (class "Default")
      (node (ref "U8") (pin "85") (pinfunction "SDA_85") (pintype "unspecified"))
    )
    (net (code "163") (name "unconnected-(U8-SLEEP-Pad41)") (class "Default")
      (node (ref "U8") (pin "41") (pinfunction "SLEEP_41") (pintype "unspecified"))
    )
    (net (code "164") (name "unconnected-(U8-SLEEP-Pad57)") (class "Default")
      (node (ref "U8") (pin "57") (pinfunction "SLEEP_57") (pintype "unspecified"))
    )
    (net (code "165") (name "unconnected-(U8-SLEEP-Pad73)") (class "Default")
      (node (ref "U8") (pin "73") (pinfunction "SLEEP_73") (pintype "unspecified"))
    )
    (net (code "166") (name "unconnected-(U8-STEP-Pad40)") (class "Default")
      (node (ref "U8") (pin "40") (pinfunction "STEP_40") (pintype "unspecified"))
    )
    (net (code "167") (name "unconnected-(U8-STEP-Pad56)") (class "Default")
      (node (ref "U8") (pin "56") (pinfunction "STEP_56") (pintype "unspecified"))
    )
    (net (code "168") (name "unconnected-(U8-STEP-Pad72)") (class "Default")
      (node (ref "U8") (pin "72") (pinfunction "STEP_72") (pintype "unspecified"))
    )
    (net (code "169") (name "unconnected-(U8-TX-Pad1)") (class "Default")
      (node (ref "U8") (pin "1") (pinfunction "TX_1") (pintype "unspecified"))
    )
    (net (code "170") (name "unconnected-(U8-TX-Pad81)") (class "Default")
      (node (ref "U8") (pin "81") (pinfunction "TX_81") (pintype "unspecified"))
    )
    (net (code "171") (name "unconnected-(U8-VDD-Pad37)") (class "Default")
      (node (ref "U8") (pin "37") (pinfunction "VDD_37") (pintype "unspecified"))
    )
    (net (code "172") (name "unconnected-(U8-VDD-Pad53)") (class "Default")
      (node (ref "U8") (pin "53") (pinfunction "VDD_53") (pintype "unspecified"))
    )
    (net (code "173") (name "unconnected-(U8-VDD-Pad69)") (class "Default")
      (node (ref "U8") (pin "69") (pinfunction "VDD_69") (pintype "unspecified"))
    )
    (net (code "174") (name "unconnected-(U8-VIN-Pad30)") (class "Default")
      (node (ref "U8") (pin "30") (pinfunction "VIN_30") (pintype "unspecified"))
    )
    (net (code "175") (name "unconnected-(U8-VIN-Pad120)") (class "Default")
      (node (ref "U8") (pin "120") (pinfunction "VIN_120") (pintype "unspecified"))
    )
    (net (code "176") (name "unconnected-(U8-VMOT-Pad31)") (class "Default")
      (node (ref "U8") (pin "31") (pinfunction "VMOT_31") (pintype "unspecified"))
    )
    (net (code "177") (name "unconnected-(U8-VMOT-Pad47)") (class "Default")
      (node (ref "U8") (pin "47") (pinfunction "VMOT_47") (pintype "unspecified"))
    )
    (net (code "178") (name "unconnected-(U8-VMOT-Pad63)") (class "Default")
      (node (ref "U8") (pin "63") (pinfunction "VMOT_63") (pintype "unspecified"))
    )
    (net (code "179") (name "unconnected-(U8-X+-Pad108)") (class "Default")
      (node (ref "U8") (pin "108") (pinfunction "X+_108") (pintype "unspecified"))
    )
    (net (code "180") (name "unconnected-(U8-X--Pad107)") (class "Default")
      (node (ref "U8") (pin "107") (pinfunction "X-_107") (pintype "unspecified"))
    )
    (net (code "181") (name "unconnected-(U8-X1-Pad91)") (class "Default")
      (node (ref "U8") (pin "91") (pinfunction "X1_91") (pintype "unspecified"))
    )
    (net (code "182") (name "unconnected-(U8-X2-Pad92)") (class "Default")
      (node (ref "U8") (pin "92") (pinfunction "X2_92") (pintype "unspecified"))
    )
    (net (code "183") (name "unconnected-(U8-X3-Pad93)") (class "Default")
      (node (ref "U8") (pin "93") (pinfunction "X3_93") (pintype "unspecified"))
    )
    (net (code "184") (name "unconnected-(U8-X4-Pad94)") (class "Default")
      (node (ref "U8") (pin "94") (pinfunction "X4_94") (pintype "unspecified"))
    )
    (net (code "185") (name "unconnected-(U8-Y+-Pad106)") (class "Default")
      (node (ref "U8") (pin "106") (pinfunction "Y+_106") (pintype "unspecified"))
    )
    (net (code "186") (name "unconnected-(U8-Y--Pad105)") (class "Default")
      (node (ref "U8") (pin "105") (pinfunction "Y-_105") (pintype "unspecified"))
    )
    (net (code "187") (name "unconnected-(U8-Y1-Pad95)") (class "Default")
      (node (ref "U8") (pin "95") (pinfunction "Y1_95") (pintype "unspecified"))
    )
    (net (code "188") (name "unconnected-(U8-Y2-Pad96)") (class "Default")
      (node (ref "U8") (pin "96") (pinfunction "Y2_96") (pintype "unspecified"))
    )
    (net (code "189") (name "unconnected-(U8-Y3-Pad97)") (class "Default")
      (node (ref "U8") (pin "97") (pinfunction "Y3_97") (pintype "unspecified"))
    )
    (net (code "190") (name "unconnected-(U8-Y4-Pad98)") (class "Default")
      (node (ref "U8") (pin "98") (pinfunction "Y4_98") (pintype "unspecified"))
    )
    (net (code "191") (name "unconnected-(U8-Z+-Pad104)") (class "Default")
      (node (ref "U8") (pin "104") (pinfunction "Z+_104") (pintype "unspecified"))
    )
    (net (code "192") (name "unconnected-(U8-Z--Pad103)") (class "Default")
      (node (ref "U8") (pin "103") (pinfunction "Z-_103") (pintype "unspecified"))
    )
    (net (code "193") (name "unconnected-(U8-Z1-Pad99)") (class "Default")
      (node (ref "U8") (pin "99") (pinfunction "Z1_99") (pintype "unspecified"))
    )
    (net (code "194") (name "unconnected-(U8-Z2-Pad100)") (class "Default")
      (node (ref "U8") (pin "100") (pinfunction "Z2_100") (pintype "unspecified"))
    )
    (net (code "195") (name "unconnected-(U8-Z3-Pad101)") (class "Default")
      (node (ref "U8") (pin "101") (pinfunction "Z3_101") (pintype "unspecified"))
    )
    (net (code "196") (name "unconnected-(U8-Z4-Pad102)") (class "Default")
      (node (ref "U8") (pin "102") (pinfunction "Z4_102") (pintype "unspecified"))
    )
  )
)
